# Burn_Wire_Dev_Board.net
KiCad netlist of a schematic drawn in Altium Designer
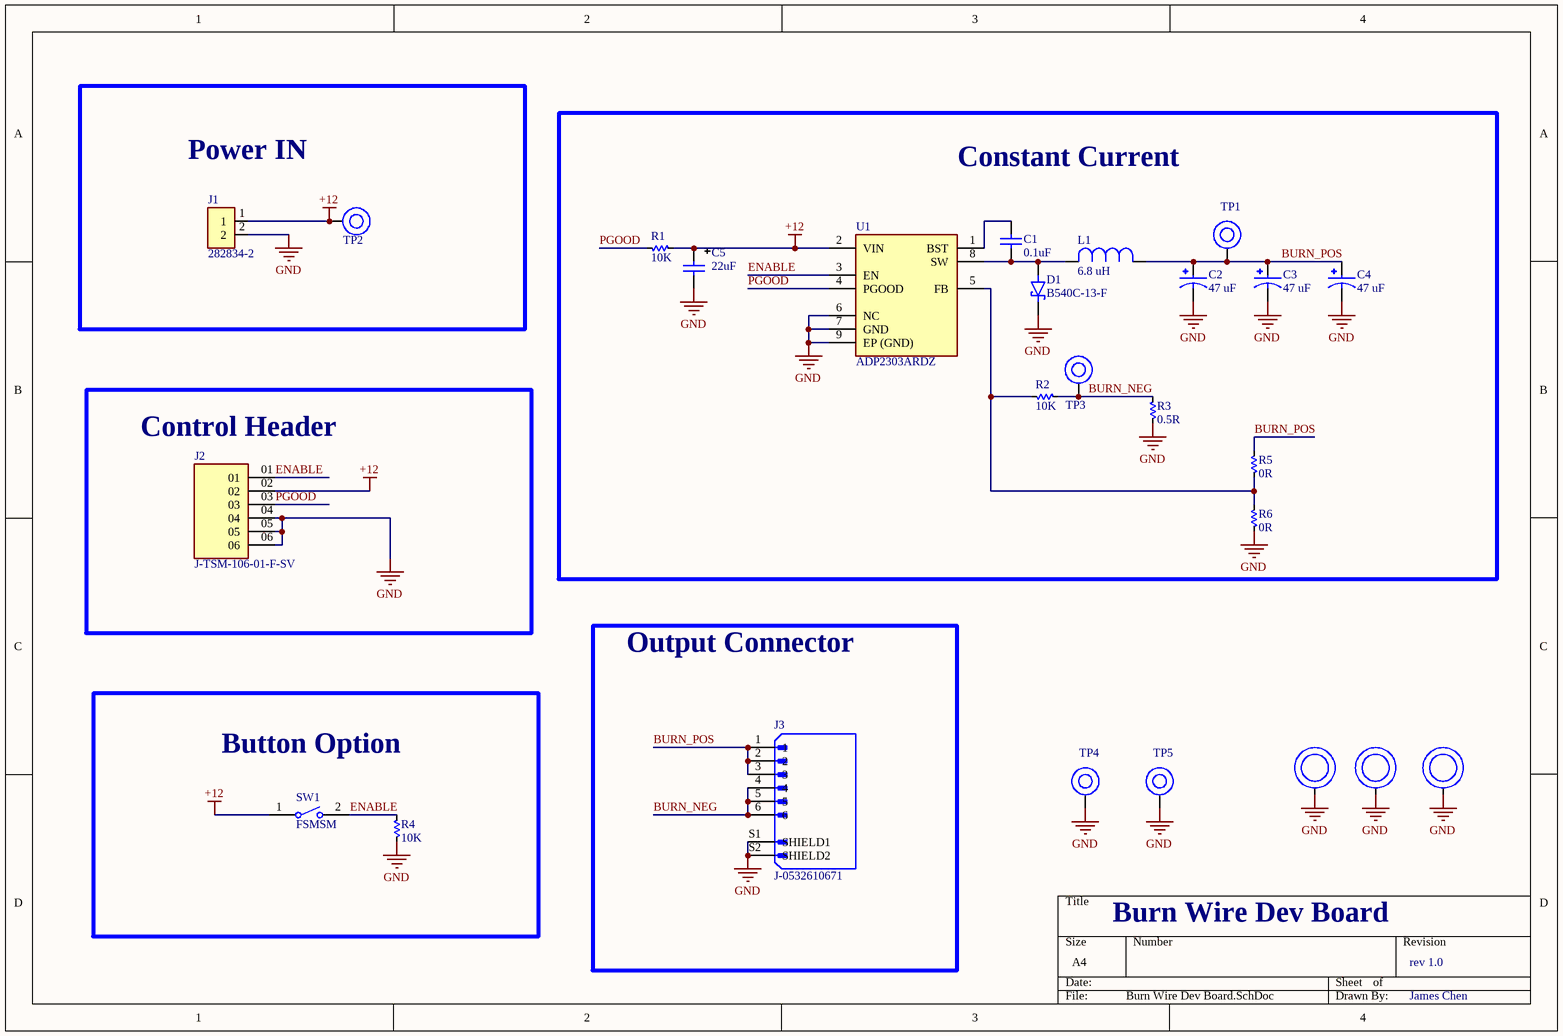
[diagram p0: Burn Wire Dev Board.SchDoc]

(export (version "E")
  (design (tool "Eeschema 10.0.6"))
  (components
    (comp (ref "*1")
      (value "M2 Mounting")
      (footprint "M2 Screws")
      (libsource (lib "RCU Board rev1.0") (part "M2 Mounting"))
    )
    (comp (ref "*2")
      (value "M2 Mounting")
      (footprint "M2 Screws")
      (libsource (lib "RCU Board rev1.0") (part "M2 Mounting"))
    )
    (comp (ref "*3")
      (value "M2 Mounting")
      (footprint "M2 Screws")
      (libsource (lib "RCU Board rev1.0") (part "M2 Mounting"))
    )
    (comp (ref "C1")
      (value "0.1uF")
      (footprint "0603")
      (description "0.1 µF ±10% 25V Ceramic Capacitor X7R 0603 (1608 Metric)")
      (fields
        (field (name "DISTRIBUTOR PART #") "1276-1006-1-ND")
        (field (name "MANUFACTURER") "Samsung Electro-Mechanics")
      )
      (libsource (lib "Burn Wire Dev Board") (part "CC-104-K-25V-X7R-0603"))
    )
    (comp (ref "C2")
      (value "47 uF")
      (footprint "CC-25SVPF47M")
      (description "CAP ALUM POLY 47UF 20% 25V SMD")
      (fields
        (field (name "DISTRIBUTOR PART #") "P16513CT-ND")
        (field (name "MANUFACTURER") "Panasonic Electronic Components")
      )
      (libsource (lib "Burn Wire Dev Board") (part "CC-25SVPF47M"))
    )
    (comp (ref "C3")
      (value "47 uF")
      (footprint "CC-25SVPF47M")
      (description "CAP ALUM POLY 47UF 20% 25V SMD")
      (fields
        (field (name "DISTRIBUTOR PART #") "P16513CT-ND")
        (field (name "MANUFACTURER") "Panasonic Electronic Components")
      )
      (libsource (lib "Burn Wire Dev Board") (part "CC-25SVPF47M"))
    )
    (comp (ref "C4")
      (value "47 uF")
      (footprint "CC-25SVPF47M")
      (description "CAP ALUM POLY 47UF 20% 25V SMD")
      (fields
        (field (name "DISTRIBUTOR PART #") "P16513CT-ND")
        (field (name "MANUFACTURER") "Panasonic Electronic Components")
      )
      (libsource (lib "Burn Wire Dev Board") (part "CC-25SVPF47M"))
    )
    (comp (ref "C5")
      (value "22uF")
      (footprint "CAP TANT 1206 (A) TCJ")
      (description "CAP TANT 22UF 10% 10V 1206")
      (fields
        (field (name "DISTRIBUTOR PART #") "478-11193-1-ND")
        (field (name "MANUFACTURER") "KYOCERA AVX")
      )
      (libsource (lib "Burn Wire Dev Board") (part "CT-225-M-20V-OTH-1206"))
    )
    (comp (ref "D1")
      (value "B540C-13-F")
      (footprint "D-B540C-13-F")
      (description "DIODE SCHOTTKY 40V 5A SMC")
      (fields
        (field (name "MANUFACTURER") "Diodes Incorporated")
        (field (name "DISTRIBUTOR PART #") "B540C-FDICT-ND")
      )
      (libsource (lib "Burn Wire Dev Board") (part "D-B540C-13-F"))
    )
    (comp (ref "J1")
      (value "282834-2")
      (footprint "J-282834-2")
      (description "TERM BLK 2P SIDE ENT 2.54MM PCB")
      (fields
        (field (name "MANUFACTURER") "TE Connectivity AMP Connectors")
        (field (name "DISTRIBUTOR PART #") "A98333-ND")
      )
      (libsource (lib "Burn Wire Dev Board") (part "J-282834-2"))
    )
    (comp (ref "J2")
      (value "J-TSM-106-01-F-SV")
      (footprint "J-TSM-106-01-F-SV")
      (description "CONN HEADER SMD 6POS 2.54MM")
      (fields (field (name "MANUFACTURER") "Samtec Inc.") (field (name "DISTRBUTOR PART #") "SAM12239-ND"))
      (libsource (lib "Burn Wire Dev Board") (part "J-TSM-106-01-F-SV"))
    )
    (comp (ref "J3")
      (value "J-0532610671")
      (footprint "J-0532610671")
      (description "CONN HEADER SMD R/A 6POS 1.25MM")
      (fields
        (field (name "MANFACTURER PART #") "0532610671")
        (field (name "DISTRIBUTOR PART #") "WM7624CT-ND")
      )
      (libsource (lib "Burn Wire Dev Board") (part "J-0532610671"))
    )
    (comp (ref "L1")
      (value "6.8 uH")
      (footprint "L-IHLP4040DZER6R8M01")
      (description "FIXED IND 6.8UH 8A 23.3 MOHM SMD")
      (fields
        (field (name "MANUFACTURER") "Vishay Dale")
        (field (name "MANUFACTURER PART #") "IHLP4040DZER6R8M01")
      )
      (libsource (lib "Burn Wire Dev Board") (part "L-IHLP4040DZER6R8M01"))
    )
    (comp (ref "R1")
      (value "10K")
      (footprint "0603")
      (description "RES 10K OHM 1% 1/8W 0603")
      (fields
        (field (name "DISTRIBUTOR PART #") "RNCP0603FTD10K0CT-ND")
        (field (name "MANUFACTURER") "Stackpole Electronics Inc")
      )
      (libsource (lib "Burn Wire Dev Board") (part "RT-10K0-F-1/16W-0603"))
    )
    (comp (ref "R2")
      (value "10K")
      (footprint "0603")
      (description "RES 10K OHM 1% 1/8W 0603")
      (fields
        (field (name "DISTRIBUTOR PART #") "RNCP0603FTD10K0CT-ND")
        (field (name "MANUFACTURER") "Stackpole Electronics Inc")
      )
      (libsource (lib "Burn Wire Dev Board") (part "RT-10K0-F-1/16W-0603"))
    )
    (comp (ref "R3")
      (value "0.5R")
      (footprint "2010")
      (description "RES 0.5 OHM 1% 1W 2010")
      (fields
        (field (name "DISTRIBUTOR PART #") "541-10112-1-ND")
        (field (name "MANUFACTURER") "Vishay Dale")
      )
      (libsource (lib "Burn Wire Dev Board") (part "RT-0.5R0-F-1W-2010"))
    )
    (comp (ref "R4")
      (value "10K")
      (footprint "0603")
      (description "RES 10K OHM 1% 1/8W 0603")
      (fields
        (field (name "DISTRIBUTOR PART #") "RNCP0603FTD10K0CT-ND")
        (field (name "MANUFACTURER") "Stackpole Electronics Inc")
      )
      (libsource (lib "Burn Wire Dev Board") (part "RT-10K0-F-1/16W-0603"))
    )
    (comp (ref "R5")
      (value "0R")
      (footprint "0603")
      (description "0 Ohms Jumper 0.1W, 1/10W Chip Resistor 0603 (1608 Metric) Automotive AEC-Q200 Thick Film")
      (fields
        (field (name "DISTRIBUTOR PART #") "RMCF0603ZT0R00CT-ND")
        (field (name "MANUFACTURER") "Stackpole Electronics Inc")
      )
      (libsource (lib "Burn Wire Dev Board") (part "RT-0R00-F-1/10W-0603"))
    )
    (comp (ref "R6")
      (value "0R")
      (footprint "0603")
      (description "0 Ohms Jumper 0.1W, 1/10W Chip Resistor 0603 (1608 Metric) Automotive AEC-Q200 Thick Film")
      (fields
        (field (name "DISTRIBUTOR PART #") "RMCF0603ZT0R00CT-ND")
        (field (name "MANUFACTURER") "Stackpole Electronics Inc")
      )
      (libsource (lib "Burn Wire Dev Board") (part "RT-0R00-F-1/10W-0603"))
    )
    (comp (ref "SW1")
      (value "FSMSM")
      (footprint "TECO-FSMSM-2_V")
      (description "FSMSM Push Button Switch, 50 mA, -35 to 85 degC, 2-Pin SMD, RoHS, Bulk")
      (fields (field (name "MANUFACTURER") "TE Connectivity"))
      (libsource (lib "Altium Content Vault") (part "SW-SPST-2_C"))
    )
    (comp (ref "TP1")
      (value "TP")
      (footprint "TP")
      (description "Test Point")
      (libsource (lib "PowerManagmentBoard_V4.0") (part "TP"))
    )
    (comp (ref "TP2")
      (value "TP")
      (footprint "TP")
      (description "Test Point")
      (libsource (lib "PowerManagmentBoard_V4.0") (part "TP"))
    )
    (comp (ref "TP3")
      (value "TP")
      (footprint "TP")
      (description "Test Point")
      (libsource (lib "PowerManagmentBoard_V4.0") (part "TP"))
    )
    (comp (ref "TP4")
      (value "TP")
      (footprint "TP")
      (description "Test Point")
      (libsource (lib "PowerManagmentBoard_V4.0") (part "TP"))
    )
    (comp (ref "TP5")
      (value "TP")
      (footprint "TP")
      (description "Test Point")
      (libsource (lib "PowerManagmentBoard_V4.0") (part "TP"))
    )
    (comp (ref "U1")
      (value "ADP2303ARDZ")
      (footprint "U-ADP2303ARDZ")
      (description "IC REG BUCK ADJUSTABLE 3A 8SOIC")
      (fields
        (field (name "MANUFACTURER") "Analog Devices Inc.")
        (field (name "DISTRIBUTOR PART #") "505-ADP2303ARDZ-ND")
      )
      (libsource (lib "Burn Wire Dev Board") (part "U-ADP2303ARDZ"))
    )
  )
  (nets
    (net (code "1") (name "+12") (class "Default")
      (node (ref "C5") (pin "1") (pinfunction "1_1") (pintype "passive"))
      (node (ref "J1") (pin "1") (pinfunction "1_1") (pintype "passive"))
      (node (ref "J2") (pin "02") (pinfunction "02_02") (pintype "passive"))
      (node (ref "R1") (pin "2") (pintype "passive"))
      (node (ref "SW1") (pin "1") (pinfunction "1_1") (pintype "passive"))
      (node (ref "TP2") (pin "1") (pinfunction "1_1") (pintype "passive"))
      (node (ref "U1") (pin "2") (pinfunction "VIN_2") (pintype "passive"))
    )
    (net (code "2") (name "/BURN_NEG") (class "Default")
      (node (ref "J3") (pin "4") (pinfunction "4_4") (pintype "passive"))
      (node (ref "J3") (pin "5") (pinfunction "5_5") (pintype "passive"))
      (node (ref "J3") (pin "6") (pinfunction "6_6") (pintype "passive"))
      (node (ref "R2") (pin "2") (pintype "passive"))
      (node (ref "R3") (pin "2") (pintype "passive"))
      (node (ref "TP3") (pin "1") (pinfunction "1_1") (pintype "passive"))
    )
    (net (code "3") (name "/BURN_POS") (class "Default")
      (node (ref "C2") (pin "1") (pinfunction "1_1") (pintype "passive"))
      (node (ref "C3") (pin "1") (pinfunction "1_1") (pintype "passive"))
      (node (ref "C4") (pin "1") (pinfunction "1_1") (pintype "passive"))
      (node (ref "J3") (pin "1") (pinfunction "1_1") (pintype "passive"))
      (node (ref "J3") (pin "2") (pinfunction "2_2") (pintype "passive"))
      (node (ref "J3") (pin "3") (pinfunction "3_3") (pintype "passive"))
      (node (ref "L1") (pin "1") (pinfunction "1_1") (pintype "passive"))
      (node (ref "R5") (pin "2") (pintype "passive"))
      (node (ref "TP1") (pin "1") (pinfunction "1_1") (pintype "passive"))
    )
    (net (code "4") (name "/ENABLE") (class "Default")
      (node (ref "J2") (pin "01") (pinfunction "01_01") (pintype "passive"))
      (node (ref "R4") (pin "2") (pintype "passive"))
      (node (ref "SW1") (pin "2") (pinfunction "2_2") (pintype "passive"))
      (node (ref "U1") (pin "3") (pinfunction "EN_3") (pintype "passive"))
    )
    (net (code "5") (name "/PGOOD") (class "Default")
      (node (ref "J2") (pin "03") (pinfunction "03_03") (pintype "passive"))
      (node (ref "R1") (pin "1") (pintype "passive"))
      (node (ref "U1") (pin "4") (pinfunction "PGOOD_4") (pintype "passive"))
    )
    (net (code "6") (name "GND") (class "Default")
      (node (ref "*1") (pin "1") (pintype "passive"))
      (node (ref "*2") (pin "1") (pintype "passive"))
      (node (ref "*3") (pin "1") (pintype "passive"))
      (node (ref "C2") (pin "2") (pinfunction "2_2") (pintype "passive"))
      (node (ref "C3") (pin "2") (pinfunction "2_2") (pintype "passive"))
      (node (ref "C4") (pin "2") (pinfunction "2_2") (pintype "passive"))
      (node (ref "C5") (pin "2") (pinfunction "2_2") (pintype "passive"))
      (node (ref "D1") (pin "C") (pinfunction "K_C") (pintype "passive"))
      (node (ref "J1") (pin "2") (pinfunction "2_2") (pintype "passive"))
      (node (ref "J2") (pin "04") (pinfunction "04_04") (pintype "passive"))
      (node (ref "J2") (pin "05") (pinfunction "05_05") (pintype "passive"))
      (node (ref "J2") (pin "06") (pinfunction "06_06") (pintype "passive"))
      (node (ref "J3") (pin "S1") (pinfunction "SHIELD1_S1") (pintype "passive"))
      (node (ref "J3") (pin "S2") (pinfunction "SHIELD2_S2") (pintype "passive"))
      (node (ref "R3") (pin "1") (pintype "passive"))
      (node (ref "R4") (pin "1") (pintype "passive"))
      (node (ref "R6") (pin "1") (pintype "passive"))
      (node (ref "TP4") (pin "1") (pinfunction "1_1") (pintype "passive"))
      (node (ref "TP5") (pin "1") (pinfunction "1_1") (pintype "passive"))
      (node (ref "U1") (pin "6") (pinfunction "NC_6") (pintype "passive"))
      (node (ref "U1") (pin "7") (pinfunction "GND_7") (pintype "passive"))
      (node (ref "U1") (pin "9") (pinfunction "EP_(GND)_9") (pintype "passive"))
    )
    (net (code "7") (name "Net-(U1-BST)") (class "Default")
      (node (ref "C1") (pin "2") (pinfunction "2_2") (pintype "passive"))
      (node (ref "U1") (pin "1") (pinfunction "BST_1") (pintype "passive"))
    )
    (net (code "8") (name "Net-(U1-FB)") (class "Default")
      (node (ref "R2") (pin "1") (pintype "passive"))
      (node (ref "R5") (pin "1") (pintype "passive"))
      (node (ref "R6") (pin "2") (pintype "passive"))
      (node (ref "U1") (pin "5") (pinfunction "FB_5") (pintype "passive"))
    )
    (net (code "9") (name "Net-(U1-SW)") (class "Default")
      (node (ref "C1") (pin "1") (pinfunction "1_1") (pintype "passive"))
      (node (ref "D1") (pin "A") (pinfunction "A_A") (pintype "passive"))
      (node (ref "L1") (pin "2") (pinfunction "2_2") (pintype "passive"))
      (node (ref "U1") (pin "8") (pinfunction "SW_8") (pintype "passive"))
    )
  )
)
